# ds2.net
KiCad netlist of a schematic drawn in EAGLE
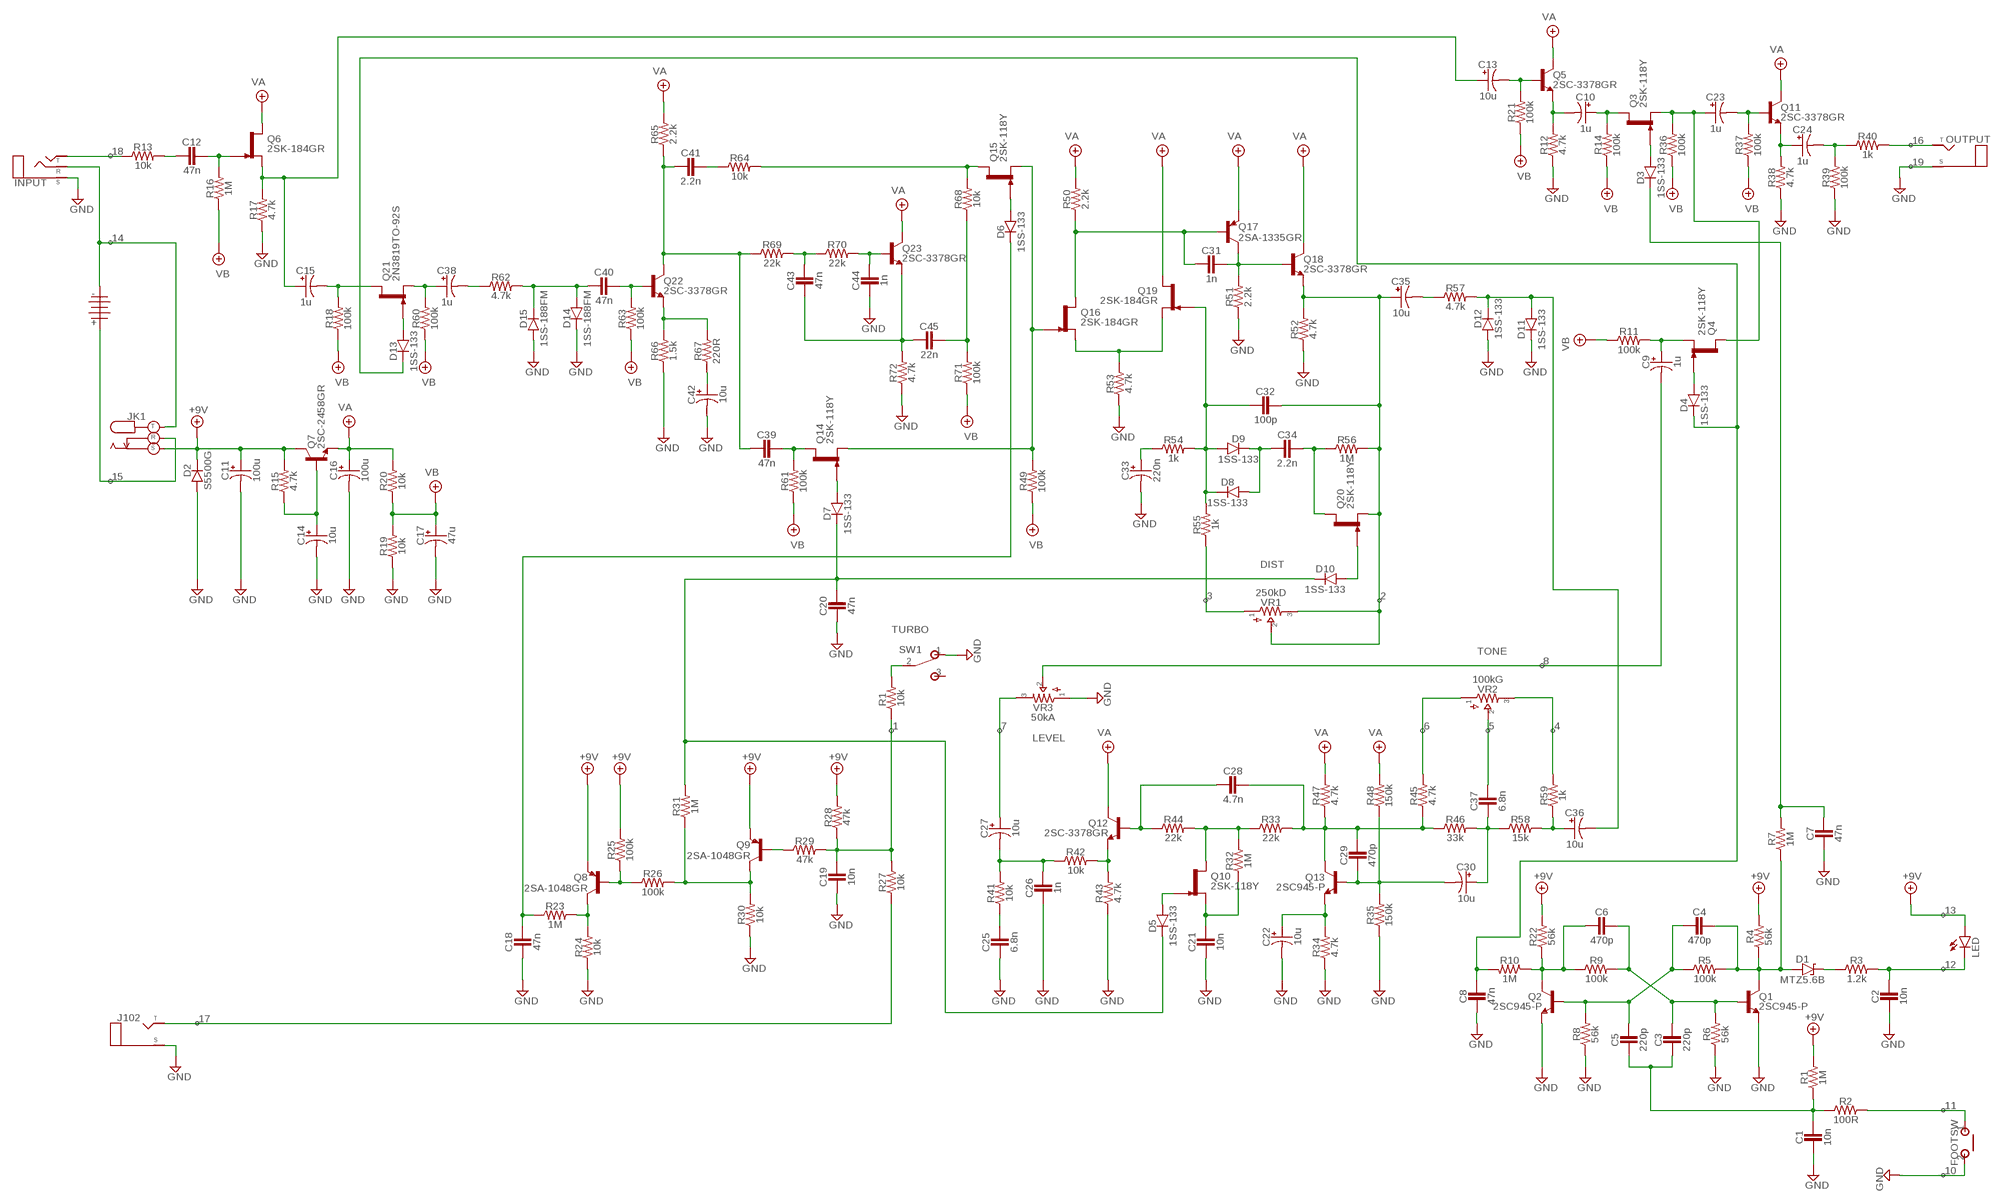
[diagram p0: schematic, sheet 1]

(export (version "E")
  (design (tool "Eeschema 10.0.6"))
  (components
    (comp (ref "1101")
      (value "BATTERY")
      (footprint "eagle-import:TWO_PADS")
      (libsource (lib "eagle-import") (part "BATTERY"))
    )
    (comp (ref "C1")
      (value "10n")
      (footprint "eagle-import:BOX_SMALL")
      (libsource (lib "eagle-import") (part "CER/FILMBOX.1"))
    )
    (comp (ref "C2")
      (value "10n")
      (footprint "eagle-import:BOX_SMALL")
      (libsource (lib "eagle-import") (part "CER/FILMBOX.1"))
    )
    (comp (ref "C3")
      (value "220p")
      (footprint "eagle-import:BOX_SMALL")
      (libsource (lib "eagle-import") (part "CER/FILMBOX.1"))
    )
    (comp (ref "C4")
      (value "470p")
      (footprint "eagle-import:BOX_SMALL")
      (libsource (lib "eagle-import") (part "CER/FILMBOX.1"))
    )
    (comp (ref "C5")
      (value "220p")
      (footprint "eagle-import:BOX_SMALL")
      (libsource (lib "eagle-import") (part "CER/FILMBOX.1"))
    )
    (comp (ref "C6")
      (value "470p")
      (footprint "eagle-import:BOX_SMALL")
      (libsource (lib "eagle-import") (part "CER/FILMBOX.1"))
    )
    (comp (ref "C7")
      (value "47n")
      (footprint "eagle-import:BOX_SMALL")
      (libsource (lib "eagle-import") (part "CER/FILMBOX.1"))
    )
    (comp (ref "C8")
      (value "47n")
      (footprint "eagle-import:BOX_SMALL")
      (libsource (lib "eagle-import") (part "CER/FILMBOX.1"))
    )
    (comp (ref "C9")
      (value "1u")
      (footprint "eagle-import:040_020")
      (libsource (lib "eagle-import") (part "0400"))
    )
    (comp (ref "C10")
      (value "1u")
      (footprint "eagle-import:040_020")
      (libsource (lib "eagle-import") (part "0400"))
    )
    (comp (ref "C11")
      (value "100u")
      (footprint "eagle-import:040_020")
      (libsource (lib "eagle-import") (part "0400"))
    )
    (comp (ref "C12")
      (value "47n")
      (footprint "eagle-import:BOX_SMALL")
      (libsource (lib "eagle-import") (part "CER/FILMBOX.1"))
    )
    (comp (ref "C13")
      (value "10u")
      (footprint "eagle-import:040_020")
      (libsource (lib "eagle-import") (part "0400"))
    )
    (comp (ref "C14")
      (value "10u")
      (footprint "eagle-import:040_020")
      (libsource (lib "eagle-import") (part "0400"))
    )
    (comp (ref "C15")
      (value "1u")
      (footprint "eagle-import:040_020")
      (libsource (lib "eagle-import") (part "0400"))
    )
    (comp (ref "C16")
      (value "100u")
      (footprint "eagle-import:040_020")
      (libsource (lib "eagle-import") (part "0400"))
    )
    (comp (ref "C17")
      (value "47u")
      (footprint "eagle-import:040_020")
      (libsource (lib "eagle-import") (part "0400"))
    )
    (comp (ref "C18")
      (value "47n")
      (footprint "eagle-import:BOX_SMALL")
      (libsource (lib "eagle-import") (part "CER/FILMBOX.1"))
    )
    (comp (ref "C19")
      (value "10n")
      (footprint "eagle-import:BOX_SMALL")
      (libsource (lib "eagle-import") (part "CER/FILMBOX.1"))
    )
    (comp (ref "C20")
      (value "47n")
      (footprint "eagle-import:BOX_SMALL")
      (libsource (lib "eagle-import") (part "CER/FILMBOX.1"))
    )
    (comp (ref "C21")
      (value "10n")
      (footprint "eagle-import:BOX_SMALL")
      (libsource (lib "eagle-import") (part "CER/FILMBOX.1"))
    )
    (comp (ref "C22")
      (value "10u")
      (footprint "eagle-import:040_020")
      (libsource (lib "eagle-import") (part "0400"))
    )
    (comp (ref "C23")
      (value "1u")
      (footprint "eagle-import:040_020")
      (libsource (lib "eagle-import") (part "0400"))
    )
    (comp (ref "C24")
      (value "1u")
      (footprint "eagle-import:040_020")
      (libsource (lib "eagle-import") (part "0400"))
    )
    (comp (ref "C25")
      (value "6.8n")
      (footprint "eagle-import:BOX_SMALL")
      (libsource (lib "eagle-import") (part "CER/FILMBOX.1"))
    )
    (comp (ref "C26")
      (value "1n")
      (footprint "eagle-import:BOX_SMALL")
      (libsource (lib "eagle-import") (part "CER/FILMBOX.1"))
    )
    (comp (ref "C27")
      (value "10u")
      (footprint "eagle-import:040_020")
      (libsource (lib "eagle-import") (part "0400"))
    )
    (comp (ref "C28")
      (value "4.7n")
      (footprint "eagle-import:BOX_SMALL")
      (libsource (lib "eagle-import") (part "CER/FILMBOX.1"))
    )
    (comp (ref "C29")
      (value "470p")
      (footprint "eagle-import:BOX_SMALL")
      (libsource (lib "eagle-import") (part "CER/FILMBOX.1"))
    )
    (comp (ref "C30")
      (value "10u")
      (footprint "eagle-import:040_020")
      (libsource (lib "eagle-import") (part "0400"))
    )
    (comp (ref "C31")
      (value "1n")
      (footprint "eagle-import:BOX_SMALL")
      (libsource (lib "eagle-import") (part "CER/FILMBOX.1"))
    )
    (comp (ref "C32")
      (value "100p")
      (footprint "eagle-import:BOX_SMALL")
      (libsource (lib "eagle-import") (part "CER/FILMBOX.1"))
    )
    (comp (ref "C33")
      (value "220n")
      (footprint "eagle-import:040_020")
      (libsource (lib "eagle-import") (part "0400"))
    )
    (comp (ref "C34")
      (value "2.2n")
      (footprint "eagle-import:BOX_SMALL")
      (libsource (lib "eagle-import") (part "CER/FILMBOX.1"))
    )
    (comp (ref "C35")
      (value "10u")
      (footprint "eagle-import:040_020")
      (libsource (lib "eagle-import") (part "0400"))
    )
    (comp (ref "C36")
      (value "10u")
      (footprint "eagle-import:040_020")
      (libsource (lib "eagle-import") (part "0400"))
    )
    (comp (ref "C37")
      (value "6.8n")
      (footprint "eagle-import:BOX_SMALL")
      (libsource (lib "eagle-import") (part "CER/FILMBOX.1"))
    )
    (comp (ref "C38")
      (value "1u")
      (footprint "eagle-import:040_020")
      (libsource (lib "eagle-import") (part "0400"))
    )
    (comp (ref "C39")
      (value "47n")
      (footprint "eagle-import:BOX_SMALL")
      (libsource (lib "eagle-import") (part "CER/FILMBOX.1"))
    )
    (comp (ref "C40")
      (value "47n")
      (footprint "eagle-import:BOX_SMALL")
      (libsource (lib "eagle-import") (part "CER/FILMBOX.1"))
    )
    (comp (ref "C41")
      (value "2.2n")
      (footprint "eagle-import:BOX_SMALL")
      (libsource (lib "eagle-import") (part "CER/FILMBOX.1"))
    )
    (comp (ref "C42")
      (value "10u")
      (footprint "eagle-import:040_020")
      (libsource (lib "eagle-import") (part "0400"))
    )
    (comp (ref "C43")
      (value "47n")
      (footprint "eagle-import:BOX_SMALL")
      (libsource (lib "eagle-import") (part "CER/FILMBOX.1"))
    )
    (comp (ref "C44")
      (value "1n")
      (footprint "eagle-import:BOX_SMALL")
      (libsource (lib "eagle-import") (part "CER/FILMBOX.1"))
    )
    (comp (ref "C45")
      (value "22n")
      (footprint "eagle-import:BOX_SMALL")
      (libsource (lib "eagle-import") (part "CER/FILMBOX.1"))
    )
    (comp (ref "D1")
      (value "MTZ5.6B")
      (footprint "eagle-import:DO41-2")
      (libsource (lib "eagle-import") (part "ZENER.2"))
    )
    (comp (ref "D2")
      (value "S5500G")
      (footprint "eagle-import:DO35-2")
      (libsource (lib "eagle-import") (part "DO35.2"))
    )
    (comp (ref "D3")
      (value "1SS-133")
      (footprint "eagle-import:DO35-2")
      (libsource (lib "eagle-import") (part "DO35.2"))
    )
    (comp (ref "D4")
      (value "1SS-133")
      (footprint "eagle-import:DO35-2")
      (libsource (lib "eagle-import") (part "DO35.2"))
    )
    (comp (ref "D5")
      (value "1SS-133")
      (footprint "eagle-import:DO35-2")
      (libsource (lib "eagle-import") (part "DO35.2"))
    )
    (comp (ref "D6")
      (value "1SS-133")
      (footprint "eagle-import:DO35-2")
      (libsource (lib "eagle-import") (part "DO35.2"))
    )
    (comp (ref "D7")
      (value "1SS-133")
      (footprint "eagle-import:DO35-2")
      (libsource (lib "eagle-import") (part "DO35.2"))
    )
    (comp (ref "D8")
      (value "1SS-133")
      (footprint "eagle-import:DO35-2")
      (libsource (lib "eagle-import") (part "DO35.2"))
    )
    (comp (ref "D9")
      (value "1SS-133")
      (footprint "eagle-import:DO35-2")
      (libsource (lib "eagle-import") (part "DO35.2"))
    )
    (comp (ref "D10")
      (value "1SS-133")
      (footprint "eagle-import:DO35-2")
      (libsource (lib "eagle-import") (part "DO35.2"))
    )
    (comp (ref "D11")
      (value "1SS-133")
      (footprint "eagle-import:DO35-2")
      (libsource (lib "eagle-import") (part "DO35.2"))
    )
    (comp (ref "D12")
      (value "1SS-133")
      (footprint "eagle-import:DO35-2")
      (libsource (lib "eagle-import") (part "DO35.2"))
    )
    (comp (ref "D13")
      (value "1SS-133")
      (footprint "eagle-import:DO35-2")
      (libsource (lib "eagle-import") (part "DO35.2"))
    )
    (comp (ref "D14")
      (value "1SS-188FM")
      (footprint "eagle-import:DO35-2")
      (libsource (lib "eagle-import") (part "DO35.2"))
    )
    (comp (ref "D15")
      (value "1SS-188FM")
      (footprint "eagle-import:DO35-2")
      (libsource (lib "eagle-import") (part "DO35.2"))
    )
    (comp (ref "FOOTSW")
      (value "MOMENTARY")
      (footprint "eagle-import:SPST")
      (libsource (lib "eagle-import") (part "MOMENTARY"))
    )
    (comp (ref "INPUT")
      (value "STEREO3PADS")
      (footprint "eagle-import:THREEPADS")
      (libsource (lib "eagle-import") (part "STEREO3PADS"))
    )
    (comp (ref "J102")
      (value "MONO")
      (footprint "eagle-import:TWO_PADS")
      (libsource (lib "eagle-import") (part "MONO"))
    )
    (comp (ref "JK1")
      (value "DC_KOBICONN")
      (footprint "eagle-import:DC_KOBICONN")
      (libsource (lib "eagle-import") (part "DC_KOBICONN"))
    )
    (comp (ref "LED")
      (value "LED")
      (footprint "eagle-import:3MM_D")
      (libsource (lib "eagle-import") (part "LED"))
    )
    (comp (ref "OUTPUT")
      (value "MONO")
      (footprint "eagle-import:TWO_PADS")
      (libsource (lib "eagle-import") (part "MONO"))
    )
    (comp (ref "Q1")
      (value "2SC945-P")
      (footprint "eagle-import:TO92-")
      (libsource (lib "eagle-import") (part "2SC828A"))
    )
    (comp (ref "Q2")
      (value "2SC945-P")
      (footprint "eagle-import:TO92-")
      (libsource (lib "eagle-import") (part "2SC828A"))
    )
    (comp (ref "Q3")
      (value "2SK-118Y")
      (footprint "eagle-import:TO92-")
      (libsource (lib "eagle-import") (part "2N3819TO-92S"))
    )
    (comp (ref "Q4")
      (value "2SK-118Y")
      (footprint "eagle-import:TO92-")
      (libsource (lib "eagle-import") (part "2N3819TO-92S"))
    )
    (comp (ref "Q5")
      (value "2SC-3378GR")
      (footprint "eagle-import:TO92-")
      (libsource (lib "eagle-import") (part "2SC828A"))
    )
    (comp (ref "Q6")
      (value "2SK-184GR")
      (footprint "eagle-import:TO92-")
      (libsource (lib "eagle-import") (part "2N3819TO-92S"))
    )
    (comp (ref "Q7")
      (value "2SC-2458GR")
      (footprint "eagle-import:TO92-")
      (libsource (lib "eagle-import") (part "2SC828A"))
    )
    (comp (ref "Q8")
      (value "2SA-1048GR")
      (footprint "eagle-import:TO92-")
      (libsource (lib "eagle-import") (part "2N3906-"))
    )
    (comp (ref "Q9")
      (value "2SA-1048GR")
      (footprint "eagle-import:TO92-")
      (libsource (lib "eagle-import") (part "2N3906-"))
    )
    (comp (ref "Q10")
      (value "2SK-118Y")
      (footprint "eagle-import:TO92-")
      (libsource (lib "eagle-import") (part "2N3819TO-92S"))
    )
    (comp (ref "Q11")
      (value "2SC-3378GR")
      (footprint "eagle-import:TO92-")
      (libsource (lib "eagle-import") (part "2SC828A"))
    )
    (comp (ref "Q12")
      (value "2SC-3378GR")
      (footprint "eagle-import:TO92-")
      (libsource (lib "eagle-import") (part "2SC828A"))
    )
    (comp (ref "Q13")
      (value "2SC945-P")
      (footprint "eagle-import:TO92-")
      (libsource (lib "eagle-import") (part "2SC828A"))
    )
    (comp (ref "Q14")
      (value "2SK-118Y")
      (footprint "eagle-import:TO92-")
      (libsource (lib "eagle-import") (part "2N3819TO-92S"))
    )
    (comp (ref "Q15")
      (value "2SK-118Y")
      (footprint "eagle-import:TO92-")
      (libsource (lib "eagle-import") (part "2N3819TO-92S"))
    )
    (comp (ref "Q16")
      (value "2SK-184GR")
      (footprint "eagle-import:TO92-")
      (libsource (lib "eagle-import") (part "2N3819TO-92S"))
    )
    (comp (ref "Q17")
      (value "2SA-1335GR")
      (footprint "eagle-import:TO92-")
      (libsource (lib "eagle-import") (part "2N3906-"))
    )
    (comp (ref "Q18")
      (value "2SC-3378GR")
      (footprint "eagle-import:TO92-")
      (libsource (lib "eagle-import") (part "2SC828A"))
    )
    (comp (ref "Q19")
      (value "2SK-184GR")
      (footprint "eagle-import:TO92-")
      (libsource (lib "eagle-import") (part "2N3819TO-92S"))
    )
    (comp (ref "Q20")
      (value "2SK-118Y")
      (footprint "eagle-import:TO92-")
      (libsource (lib "eagle-import") (part "2N3819TO-92S"))
    )
    (comp (ref "Q21")
      (value "2N3819TO-92S")
      (footprint "eagle-import:TO92-")
      (libsource (lib "eagle-import") (part "2N3819TO-92S"))
    )
    (comp (ref "Q22")
      (value "2SC-3378GR")
      (footprint "eagle-import:TO92-")
      (libsource (lib "eagle-import") (part "2SC828A"))
    )
    (comp (ref "Q23")
      (value "2SC-3378GR")
      (footprint "eagle-import:TO92-")
      (libsource (lib "eagle-import") (part "2SC828A"))
    )
    (comp (ref "R1")
      (value "1M")
      (footprint "eagle-import:R0207_3")
      (libsource (lib "eagle-import") (part "R_.3B"))
    )
    (comp (ref "R1 ")
      (value "10k")
      (footprint "eagle-import:R0207_3")
      (libsource (lib "eagle-import") (part "R_.3B"))
    )
    (comp (ref "R2")
      (value "100R")
      (footprint "eagle-import:R0207_3")
      (libsource (lib "eagle-import") (part "R_.3B"))
    )
    (comp (ref "R3")
      (value "1.2k")
      (footprint "eagle-import:R0207_3")
      (libsource (lib "eagle-import") (part "R_.3B"))
    )
    (comp (ref "R4")
      (value "56k")
      (footprint "eagle-import:R0207_3")
      (libsource (lib "eagle-import") (part "R_.3B"))
    )
    (comp (ref "R5")
      (value "100k")
      (footprint "eagle-import:R0207_3")
      (libsource (lib "eagle-import") (part "R_.3B"))
    )
    (comp (ref "R6")
      (value "56k")
      (footprint "eagle-import:R0207_3")
      (libsource (lib "eagle-import") (part "R_.3B"))
    )
    (comp (ref "R7")
      (value "1M")
      (footprint "eagle-import:R0207_3")
      (libsource (lib "eagle-import") (part "R_.3B"))
    )
    (comp (ref "R8")
      (value "56k")
      (footprint "eagle-import:R0207_3")
      (libsource (lib "eagle-import") (part "R_.3B"))
    )
    (comp (ref "R9")
      (value "100k")
      (footprint "eagle-import:R0207_3")
      (libsource (lib "eagle-import") (part "R_.3B"))
    )
    (comp (ref "R10")
      (value "1M")
      (footprint "eagle-import:R0207_3")
      (libsource (lib "eagle-import") (part "R_.3B"))
    )
    (comp (ref "R11")
      (value "100k")
      (footprint "eagle-import:R0207_3")
      (libsource (lib "eagle-import") (part "R_.3B"))
    )
    (comp (ref "R12")
      (value "4.7k")
      (footprint "eagle-import:R0207_3")
      (libsource (lib "eagle-import") (part "R_.3B"))
    )
    (comp (ref "R13")
      (value "10k")
      (footprint "eagle-import:R0207_3")
      (libsource (lib "eagle-import") (part "R_.3B"))
    )
    (comp (ref "R14")
      (value "100k")
      (footprint "eagle-import:R0207_3")
      (libsource (lib "eagle-import") (part "R_.3B"))
    )
    (comp (ref "R15")
      (value "4.7k")
      (footprint "eagle-import:R0207_3")
      (libsource (lib "eagle-import") (part "R_.3B"))
    )
    (comp (ref "R16")
      (value "1M")
      (footprint "eagle-import:R0207_3")
      (libsource (lib "eagle-import") (part "R_.3B"))
    )
    (comp (ref "R17")
      (value "4.7k")
      (footprint "eagle-import:R0207_3")
      (libsource (lib "eagle-import") (part "R_.3B"))
    )
    (comp (ref "R18")
      (value "100k")
      (footprint "eagle-import:R0207_3")
      (libsource (lib "eagle-import") (part "R_.3B"))
    )
    (comp (ref "R19")
      (value "10k")
      (footprint "eagle-import:R0207_3")
      (libsource (lib "eagle-import") (part "R_.3B"))
    )
    (comp (ref "R20")
      (value "10k")
      (footprint "eagle-import:R0207_3")
      (libsource (lib "eagle-import") (part "R_.3B"))
    )
    (comp (ref "R21")
      (value "100k")
      (footprint "eagle-import:R0207_3")
      (libsource (lib "eagle-import") (part "R_.3B"))
    )
    (comp (ref "R22")
      (value "56k")
      (footprint "eagle-import:R0207_3")
      (libsource (lib "eagle-import") (part "R_.3B"))
    )
    (comp (ref "R23")
      (value "1M")
      (footprint "eagle-import:R0207_3")
      (libsource (lib "eagle-import") (part "R_.3B"))
    )
    (comp (ref "R24")
      (value "10k")
      (footprint "eagle-import:R0207_3")
      (libsource (lib "eagle-import") (part "R_.3B"))
    )
    (comp (ref "R25")
      (value "100k")
      (footprint "eagle-import:R0207_3")
      (libsource (lib "eagle-import") (part "R_.3B"))
    )
    (comp (ref "R26")
      (value "100k")
      (footprint "eagle-import:R0207_3")
      (libsource (lib "eagle-import") (part "R_.3B"))
    )
    (comp (ref "R27")
      (value "10k")
      (footprint "eagle-import:R0207_3")
      (libsource (lib "eagle-import") (part "R_.3B"))
    )
    (comp (ref "R28")
      (value "47k")
      (footprint "eagle-import:R0207_3")
      (libsource (lib "eagle-import") (part "R_.3B"))
    )
    (comp (ref "R29")
      (value "47k")
      (footprint "eagle-import:R0207_3")
      (libsource (lib "eagle-import") (part "R_.3B"))
    )
    (comp (ref "R30")
      (value "10k")
      (footprint "eagle-import:R0207_3")
      (libsource (lib "eagle-import") (part "R_.3B"))
    )
    (comp (ref "R31")
      (value "1M")
      (footprint "eagle-import:R0207_3")
      (libsource (lib "eagle-import") (part "R_.3B"))
    )
    (comp (ref "R32")
      (value "1M")
      (footprint "eagle-import:R0207_3")
      (libsource (lib "eagle-import") (part "R_.3B"))
    )
    (comp (ref "R33")
      (value "22k")
      (footprint "eagle-import:R0207_3")
      (libsource (lib "eagle-import") (part "R_.3B"))
    )
    (comp (ref "R34")
      (value "4.7k")
      (footprint "eagle-import:R0207_3")
      (libsource (lib "eagle-import") (part "R_.3B"))
    )
    (comp (ref "R35")
      (value "150k")
      (footprint "eagle-import:R0207_3")
      (libsource (lib "eagle-import") (part "R_.3B"))
    )
    (comp (ref "R36")
      (value "100k")
      (footprint "eagle-import:R0207_3")
      (libsource (lib "eagle-import") (part "R_.3B"))
    )
    (comp (ref "R37")
      (value "100k")
      (footprint "eagle-import:R0207_3")
      (libsource (lib "eagle-import") (part "R_.3B"))
    )
    (comp (ref "R38")
      (value "4.7k")
      (footprint "eagle-import:R0207_3")
      (libsource (lib "eagle-import") (part "R_.3B"))
    )
    (comp (ref "R39")
      (value "100k")
      (footprint "eagle-import:R0207_3")
      (libsource (lib "eagle-import") (part "R_.3B"))
    )
    (comp (ref "R40")
      (value "1k")
      (footprint "eagle-import:R0207_3")
      (libsource (lib "eagle-import") (part "R_.3B"))
    )
    (comp (ref "R41")
      (value "10k")
      (footprint "eagle-import:R0207_3")
      (libsource (lib "eagle-import") (part "R_.3B"))
    )
    (comp (ref "R42")
      (value "10k")
      (footprint "eagle-import:R0207_3")
      (libsource (lib "eagle-import") (part "R_.3B"))
    )
    (comp (ref "R43")
      (value "4.7k")
      (footprint "eagle-import:R0207_3")
      (libsource (lib "eagle-import") (part "R_.3B"))
    )
    (comp (ref "R44")
      (value "22k")
      (footprint "eagle-import:R0207_3")
      (libsource (lib "eagle-import") (part "R_.3B"))
    )
    (comp (ref "R45")
      (value "4.7k")
      (footprint "eagle-import:R0207_3")
      (libsource (lib "eagle-import") (part "R_.3B"))
    )
    (comp (ref "R46")
      (value "33k")
      (footprint "eagle-import:R0207_3")
      (libsource (lib "eagle-import") (part "R_.3B"))
    )
    (comp (ref "R47")
      (value "4.7k")
      (footprint "eagle-import:R0207_3")
      (libsource (lib "eagle-import") (part "R_.3B"))
    )
    (comp (ref "R48")
      (value "150k")
      (footprint "eagle-import:R0207_3")
      (libsource (lib "eagle-import") (part "R_.3B"))
    )
    (comp (ref "R49")
      (value "100k")
      (footprint "eagle-import:R0207_3")
      (libsource (lib "eagle-import") (part "R_.3B"))
    )
    (comp (ref "R50")
      (value "2.2k")
      (footprint "eagle-import:R0207_3")
      (libsource (lib "eagle-import") (part "R_.3B"))
    )
    (comp (ref "R51")
      (value "2.2k")
      (footprint "eagle-import:R0207_3")
      (libsource (lib "eagle-import") (part "R_.3B"))
    )
    (comp (ref "R52")
      (value "4.7k")
      (footprint "eagle-import:R0207_3")
      (libsource (lib "eagle-import") (part "R_.3B"))
    )
    (comp (ref "R53")
      (value "4.7k")
      (footprint "eagle-import:R0207_3")
      (libsource (lib "eagle-import") (part "R_.3B"))
    )
    (comp (ref "R54")
      (value "1k")
      (footprint "eagle-import:R0207_3")
      (libsource (lib "eagle-import") (part "R_.3B"))
    )
    (comp (ref "R55")
      (value "1k")
      (footprint "eagle-import:R0207_3")
      (libsource (lib "eagle-import") (part "R_.3B"))
    )
    (comp (ref "R56")
      (value "1M")
      (footprint "eagle-import:R0207_3")
      (libsource (lib "eagle-import") (part "R_.3B"))
    )
    (comp (ref "R57")
      (value "4.7k")
      (footprint "eagle-import:R0207_3")
      (libsource (lib "eagle-import") (part "R_.3B"))
    )
    (comp (ref "R58")
      (value "15k")
      (footprint "eagle-import:R0207_3")
      (libsource (lib "eagle-import") (part "R_.3B"))
    )
    (comp (ref "R59")
      (value "1k")
      (footprint "eagle-import:R0207_3")
      (libsource (lib "eagle-import") (part "R_.3B"))
    )
    (comp (ref "R60")
      (value "100k")
      (footprint "eagle-import:R0207_3")
      (libsource (lib "eagle-import") (part "R_.3B"))
    )
    (comp (ref "R61")
      (value "100k")
      (footprint "eagle-import:R0207_3")
      (libsource (lib "eagle-import") (part "R_.3B"))
    )
    (comp (ref "R62")
      (value "4.7k")
      (footprint "eagle-import:R0207_3")
      (libsource (lib "eagle-import") (part "R_.3B"))
    )
    (comp (ref "R63")
      (value "100k")
      (footprint "eagle-import:R0207_3")
      (libsource (lib "eagle-import") (part "R_.3B"))
    )
    (comp (ref "R64")
      (value "10k")
      (footprint "eagle-import:R0207_3")
      (libsource (lib "eagle-import") (part "R_.3B"))
    )
    (comp (ref "R65")
      (value "2.2k")
      (footprint "eagle-import:R0207_3")
      (libsource (lib "eagle-import") (part "R_.3B"))
    )
    (comp (ref "R66")
      (value "1.5k")
      (footprint "eagle-import:R0207_3")
      (libsource (lib "eagle-import") (part "R_.3B"))
    )
    (comp (ref "R67")
      (value "220R")
      (footprint "eagle-import:R0207_3")
      (libsource (lib "eagle-import") (part "R_.3B"))
    )
    (comp (ref "R68")
      (value "10k")
      (footprint "eagle-import:R0207_3")
      (libsource (lib "eagle-import") (part "R_.3B"))
    )
    (comp (ref "R69")
      (value "22k")
      (footprint "eagle-import:R0207_3")
      (libsource (lib "eagle-import") (part "R_.3B"))
    )
    (comp (ref "R70")
      (value "22k")
      (footprint "eagle-import:R0207_3")
      (libsource (lib "eagle-import") (part "R_.3B"))
    )
    (comp (ref "R71")
      (value "100k")
      (footprint "eagle-import:R0207_3")
      (libsource (lib "eagle-import") (part "R_.3B"))
    )
    (comp (ref "R72")
      (value "4.7k")
      (footprint "eagle-import:R0207_3")
      (libsource (lib "eagle-import") (part "R_.3B"))
    )
    (comp (ref "SW1")
      (value "SPDT")
      (footprint "eagle-import:M9040P")
      (libsource (lib "eagle-import") (part "SPDT"))
    )
    (comp (ref "VR1")
      (value "250kD")
      (footprint "eagle-import:16MM")
      (libsource (lib "eagle-import") (part "POTS16MM"))
    )
    (comp (ref "VR2")
      (value "100kG")
      (footprint "eagle-import:16MM")
      (libsource (lib "eagle-import") (part "POTS16MM"))
    )
    (comp (ref "VR3")
      (value "50kA")
      (footprint "eagle-import:16MM")
      (libsource (lib "eagle-import") (part "POTS16MM"))
    )
  )
  (nets
    (net (code "1") (name "+9V") (class "Default")
      (node (ref "C11") (pin "+") (pinfunction "+_+") (pintype "passive"))
      (node (ref "D2") (pin "C") (pinfunction "C_C") (pintype "passive"))
      (node (ref "JK1") (pin "S") (pinfunction "S_S") (pintype "bidirectional"))
      (node (ref "LED") (pin "ANODE") (pinfunction "A_ANODE") (pintype "passive"))
      (node (ref "Q7") (pin "2") (pinfunction "C_2") (pintype "passive"))
      (node (ref "Q8") (pin "3") (pinfunction "E_3") (pintype "passive"))
      (node (ref "Q9") (pin "3") (pinfunction "E_3") (pintype "passive"))
      (node (ref "R1") (pin "2") (pinfunction "2_2") (pintype "passive"))
      (node (ref "R15") (pin "2") (pinfunction "2_2") (pintype "passive"))
      (node (ref "R22") (pin "2") (pinfunction "2_2") (pintype "passive"))
      (node (ref "R25") (pin "2") (pinfunction "2_2") (pintype "passive"))
      (node (ref "R28") (pin "2") (pinfunction "2_2") (pintype "passive"))
      (node (ref "R4") (pin "2") (pinfunction "2_2") (pintype "passive"))
    )
    (net (code "2") (name "GND") (class "Default")
      (node (ref "C1") (pin "2") (pinfunction "2_2") (pintype "passive"))
      (node (ref "C11") (pin "-") (pinfunction "-_-") (pintype "passive"))
      (node (ref "C14") (pin "-") (pinfunction "-_-") (pintype "passive"))
      (node (ref "C16") (pin "-") (pinfunction "-_-") (pintype "passive"))
      (node (ref "C17") (pin "-") (pinfunction "-_-") (pintype "passive"))
      (node (ref "C18") (pin "2") (pinfunction "2_2") (pintype "passive"))
      (node (ref "C19") (pin "2") (pinfunction "2_2") (pintype "passive"))
      (node (ref "C2") (pin "2") (pinfunction "2_2") (pintype "passive"))
      (node (ref "C20") (pin "2") (pinfunction "2_2") (pintype "passive"))
      (node (ref "C21") (pin "2") (pinfunction "2_2") (pintype "passive"))
      (node (ref "C22") (pin "-") (pinfunction "-_-") (pintype "passive"))
      (node (ref "C25") (pin "2") (pinfunction "2_2") (pintype "passive"))
      (node (ref "C26") (pin "2") (pinfunction "2_2") (pintype "passive"))
      (node (ref "C33") (pin "-") (pinfunction "-_-") (pintype "passive"))
      (node (ref "C42") (pin "-") (pinfunction "-_-") (pintype "passive"))
      (node (ref "C44") (pin "2") (pinfunction "2_2") (pintype "passive"))
      (node (ref "C7") (pin "2") (pinfunction "2_2") (pintype "passive"))
      (node (ref "C8") (pin "2") (pinfunction "2_2") (pintype "passive"))
      (node (ref "D11") (pin "C") (pinfunction "C_C") (pintype "passive"))
      (node (ref "D12") (pin "A") (pinfunction "A_A") (pintype "passive"))
      (node (ref "D14") (pin "C") (pinfunction "C_C") (pintype "passive"))
      (node (ref "D15") (pin "A") (pinfunction "A_A") (pintype "passive"))
      (node (ref "D2") (pin "A") (pinfunction "A_A") (pintype "passive"))
      (node (ref "FOOTSW") (pin "2") (pinfunction "S_2") (pintype "passive"))
      (node (ref "INPUT") (pin "SLEEVE") (pinfunction "S_SLEEVE") (pintype "passive"))
      (node (ref "J102") (pin "S") (pinfunction "SLEEVE_S") (pintype "passive"))
      (node (ref "OUTPUT") (pin "S") (pinfunction "SLEEVE_S") (pintype "passive"))
      (node (ref "Q1") (pin "3") (pinfunction "E_3") (pintype "passive"))
      (node (ref "Q2") (pin "3") (pinfunction "E_3") (pintype "passive"))
      (node (ref "R12") (pin "1") (pinfunction "1_1") (pintype "passive"))
      (node (ref "R17") (pin "1") (pinfunction "1_1") (pintype "passive"))
      (node (ref "R19") (pin "1") (pinfunction "1_1") (pintype "passive"))
      (node (ref "R24") (pin "1") (pinfunction "1_1") (pintype "passive"))
      (node (ref "R30") (pin "1") (pinfunction "1_1") (pintype "passive"))
      (node (ref "R34") (pin "1") (pinfunction "1_1") (pintype "passive"))
      (node (ref "R35") (pin "1") (pinfunction "1_1") (pintype "passive"))
      (node (ref "R38") (pin "1") (pinfunction "1_1") (pintype "passive"))
      (node (ref "R39") (pin "1") (pinfunction "1_1") (pintype "passive"))
      (node (ref "R43") (pin "1") (pinfunction "1_1") (pintype "passive"))
      (node (ref "R51") (pin "1") (pinfunction "1_1") (pintype "passive"))
      (node (ref "R52") (pin "1") (pinfunction "1_1") (pintype "passive"))
      (node (ref "R53") (pin "1") (pinfunction "1_1") (pintype "passive"))
      (node (ref "R6") (pin "1") (pinfunction "1_1") (pintype "passive"))
      (node (ref "R66") (pin "1") (pinfunction "1_1") (pintype "passive"))
      (node (ref "R72") (pin "1") (pinfunction "1_1") (pintype "passive"))
      (node (ref "R8") (pin "1") (pinfunction "1_1") (pintype "passive"))
      (node (ref "SW1") (pin "1") (pinfunction "O_1") (pintype "passive"))
      (node (ref "VR3") (pin "1") (pinfunction "1_1") (pintype "passive"))
    )
    (net (code "3") (name "Net-(1101-P$1)") (class "Default")
      (node (ref "1101") (pin "T") (pinfunction "P$1_T") (pintype "bidirectional"))
      (node (ref "JK1") (pin "R") (pinfunction "R_R") (pintype "bidirectional"))
    )
    (net (code "4") (name "Net-(1101-P$2)") (class "Default")
      (node (ref "1101") (pin "S") (pinfunction "P$2_S") (pintype "bidirectional"))
      (node (ref "INPUT") (pin "RING") (pinfunction "R_RING") (pintype "passive"))
      (node (ref "JK1") (pin "T") (pinfunction "T_T") (pintype "bidirectional"))
    )
    (net (code "5") (name "Net-(C1-Pad1)") (class "Default")
      (node (ref "C1") (pin "1") (pinfunction "1_1") (pintype "passive"))
      (node (ref "C3") (pin "2") (pinfunction "2_2") (pintype "passive"))
      (node (ref "C5") (pin "2") (pinfunction "2_2") (pintype "passive"))
      (node (ref "R1") (pin "1") (pinfunction "1_1") (pintype "passive"))
      (node (ref "R2") (pin "1") (pinfunction "1_1") (pintype "passive"))
    )
    (net (code "6") (name "Net-(C7-Pad1)") (class "Default")
      (node (ref "C7") (pin "1") (pinfunction "1_1") (pintype "passive"))
      (node (ref "D3") (pin "C") (pinfunction "C_C") (pintype "passive"))
      (node (ref "R7") (pin "2") (pinfunction "2_2") (pintype "passive"))
    )
    (net (code "7") (name "Net-(C8-Pad1)") (class "Default")
      (node (ref "C8") (pin "1") (pinfunction "1_1") (pintype "passive"))
      (node (ref "D13") (pin "C") (pinfunction "C_C") (pintype "passive"))
      (node (ref "D4") (pin "C") (pinfunction "C_C") (pintype "passive"))
      (node (ref "R10") (pin "2") (pinfunction "2_2") (pintype "passive"))
    )
    (net (code "8") (name "Net-(C9-Pad-)") (class "Default")
      (node (ref "C9") (pin "-") (pinfunction "-_-") (pintype "passive"))
      (node (ref "VR3") (pin "2") (pinfunction "2_2") (pintype "passive"))
    )
    (net (code "9") (name "Net-(C12-Pad2)") (class "Default")
      (node (ref "C12") (pin "2") (pinfunction "2_2") (pintype "passive"))
      (node (ref "R13") (pin "2") (pinfunction "2_2") (pintype "passive"))
    )
    (net (code "10") (name "Net-(C18-Pad1)") (class "Default")
      (node (ref "C18") (pin "1") (pinfunction "1_1") (pintype "passive"))
      (node (ref "D6") (pin "C") (pinfunction "C_C") (pintype "passive"))
      (node (ref "R23") (pin "1") (pinfunction "1_1") (pintype "passive"))
    )
    (net (code "11") (name "Net-(C19-Pad1)") (class "Default")
      (node (ref "C19") (pin "1") (pinfunction "1_1") (pintype "passive"))
      (node (ref "R1 ") (pin "1") (pinfunction "1_1") (pintype "passive"))
      (node (ref "R27") (pin "2") (pinfunction "2_2") (pintype "passive"))
      (node (ref "R28") (pin "1") (pinfunction "1_1") (pintype "passive"))
      (node (ref "R29") (pin "2") (pinfunction "2_2") (pintype "passive"))
    )
    (net (code "12") (name "Net-(C20-Pad1)") (class "Default")
      (node (ref "C20") (pin "1") (pinfunction "1_1") (pintype "passive"))
      (node (ref "D10") (pin "C") (pinfunction "C_C") (pintype "passive"))
      (node (ref "D5") (pin "C") (pinfunction "C_C") (pintype "passive"))
      (node (ref "D7") (pin "C") (pinfunction "C_C") (pintype "passive"))
      (node (ref "R31") (pin "2") (pinfunction "2_2") (pintype "passive"))
    )
    (net (code "13") (name "Net-(C24-Pad-)") (class "Default")
      (node (ref "C24") (pin "-") (pinfunction "-_-") (pintype "passive"))
      (node (ref "R39") (pin "2") (pinfunction "2_2") (pintype "passive"))
      (node (ref "R40") (pin "1") (pinfunction "1_1") (pintype "passive"))
    )
    (net (code "14") (name "Net-(C25-Pad1)") (class "Default")
      (node (ref "C25") (pin "1") (pinfunction "1_1") (pintype "passive"))
      (node (ref "R41") (pin "1") (pinfunction "1_1") (pintype "passive"))
    )
    (net (code "15") (name "Net-(C26-Pad1)") (class "Default")
      (node (ref "C26") (pin "1") (pinfunction "1_1") (pintype "passive"))
      (node (ref "C27") (pin "-") (pinfunction "-_-") (pintype "passive"))
      (node (ref "R41") (pin "2") (pinfunction "2_2") (pintype "passive"))
      (node (ref "R42") (pin "1") (pinfunction "1_1") (pintype "passive"))
    )
    (net (code "16") (name "Net-(C27-Pad+)") (class "Default")
      (node (ref "C27") (pin "+") (pinfunction "+_+") (pintype "passive"))
      (node (ref "VR3") (pin "3") (pinfunction "3_3") (pintype "passive"))
    )
    (net (code "17") (name "Net-(C30-Pad+)") (class "Default")
      (node (ref "C30") (pin "+") (pinfunction "+_+") (pintype "passive"))
      (node (ref "C37") (pin "2") (pinfunction "2_2") (pintype "passive"))
      (node (ref "R46") (pin "2") (pinfunction "2_2") (pintype "passive"))
      (node (ref "R58") (pin "1") (pinfunction "1_1") (pintype "passive"))
    )
    (net (code "18") (name "Net-(C33-Pad+)") (class "Default")
      (node (ref "C33") (pin "+") (pinfunction "+_+") (pintype "passive"))
      (node (ref "R54") (pin "1") (pinfunction "1_1") (pintype "passive"))
    )
    (net (code "19") (name "Net-(C34-Pad2)") (class "Default")
      (node (ref "C34") (pin "2") (pinfunction "2_2") (pintype "passive"))
      (node (ref "D8") (pin "A") (pinfunction "A_A") (pintype "passive"))
      (node (ref "D9") (pin "C") (pinfunction "C_C") (pintype "passive"))
    )
    (net (code "20") (name "Net-(C35-Pad-)") (class "Default")
      (node (ref "C35") (pin "-") (pinfunction "-_-") (pintype "passive"))
      (node (ref "R57") (pin "1") (pinfunction "1_1") (pintype "passive"))
    )
    (net (code "21") (name "Net-(C36-Pad+)") (class "Default")
      (node (ref "C36") (pin "+") (pinfunction "+_+") (pintype "passive"))
      (node (ref "R58") (pin "2") (pinfunction "2_2") (pintype "passive"))
      (node (ref "R59") (pin "1") (pinfunction "1_1") (pintype "passive"))
    )
    (net (code "22") (name "Net-(C36-Pad-)") (class "Default")
      (node (ref "C36") (pin "-") (pinfunction "-_-") (pintype "passive"))
      (node (ref "D11") (pin "A") (pinfunction "A_A") (pintype "passive"))
      (node (ref "D12") (pin "C") (pinfunction "C_C") (pintype "passive"))
      (node (ref "R57") (pin "2") (pinfunction "2_2") (pintype "passive"))
    )
    (net (code "23") (name "Net-(C37-Pad1)") (class "Default")
      (node (ref "C37") (pin "1") (pinfunction "1_1") (pintype "passive"))
      (node (ref "VR2") (pin "2") (pinfunction "2_2") (pintype "passive"))
    )
    (net (code "24") (name "Net-(C38-Pad-)") (class "Default")
      (node (ref "C38") (pin "-") (pinfunction "-_-") (pintype "passive"))
      (node (ref "R62") (pin "1") (pinfunction "1_1") (pintype "passive"))
    )
    (net (code "25") (name "Net-(C40-Pad2)") (class "Default")
      (node (ref "C40") (pin "2") (pinfunction "2_2") (pintype "passive"))
      (node (ref "D14") (pin "A") (pinfunction "A_A") (pintype "passive"))
      (node (ref "D15") (pin "C") (pinfunction "C_C") (pintype "passive"))
      (node (ref "R62") (pin "2") (pinfunction "2_2") (pintype "passive"))
    )
    (net (code "26") (name "Net-(C41-Pad1)") (class "Default")
      (node (ref "C41") (pin "1") (pinfunction "1_1") (pintype "passive"))
      (node (ref "R64") (pin "1") (pinfunction "1_1") (pintype "passive"))
    )
    (net (code "27") (name "Net-(C42-Pad+)") (class "Default")
      (node (ref "C42") (pin "+") (pinfunction "+_+") (pintype "passive"))
      (node (ref "R67") (pin "1") (pinfunction "1_1") (pintype "passive"))
    )
    (net (code "28") (name "Net-(C43-Pad1)") (class "Default")
      (node (ref "C43") (pin "1") (pinfunction "1_1") (pintype "passive"))
      (node (ref "R69") (pin "2") (pinfunction "2_2") (pintype "passive"))
      (node (ref "R70") (pin "1") (pinfunction "1_1") (pintype "passive"))
    )
    (net (code "29") (name "Net-(C45-Pad1)") (class "Default")
      (node (ref "C45") (pin "1") (pinfunction "1_1") (pintype "passive"))
      (node (ref "R68") (pin "1") (pinfunction "1_1") (pintype "passive"))
      (node (ref "R71") (pin "2") (pinfunction "2_2") (pintype "passive"))
    )
    (net (code "30") (name "Net-(D1-PadC)") (class "Default")
      (node (ref "D1") (pin "C") (pinfunction "C_C") (pintype "passive"))
      (node (ref "R3") (pin "1") (pinfunction "1_1") (pintype "passive"))
    )
    (net (code "31") (name "Net-(FOOTSW-P)") (class "Default")
      (node (ref "FOOTSW") (pin "1") (pinfunction "P_1") (pintype "passive"))
      (node (ref "R2") (pin "2") (pinfunction "2_2") (pintype "passive"))
    )
    (net (code "32") (name "Net-(INPUT-T)") (class "Default")
      (node (ref "INPUT") (pin "TIP") (pinfunction "T_TIP") (pintype "passive"))
      (node (ref "R13") (pin "1") (pinfunction "1_1") (pintype "passive"))
    )
    (net (code "33") (name "Net-(J102-TIP)") (class "Default")
      (node (ref "J102") (pin "T") (pinfunction "TIP_T") (pintype "passive"))
      (node (ref "R27") (pin "1") (pinfunction "1_1") (pintype "passive"))
    )
    (net (code "34") (name "Net-(LED-C)") (class "Default")
      (node (ref "C2") (pin "1") (pinfunction "1_1") (pintype "passive"))
      (node (ref "LED") (pin "P$1") (pinfunction "C_P$1") (pintype "passive"))
      (node (ref "R3") (pin "2") (pinfunction "2_2") (pintype "passive"))
    )
    (net (code "35") (name "Net-(OUTPUT-TIP)") (class "Default")
      (node (ref "OUTPUT") (pin "T") (pinfunction "TIP_T") (pintype "passive"))
      (node (ref "R40") (pin "2") (pinfunction "2_2") (pintype "passive"))
    )
    (net (code "36") (name "Net-(Q1-B)") (class "Default")
      (node (ref "C3") (pin "1") (pinfunction "1_1") (pintype "passive"))
      (node (ref "C6") (pin "1") (pinfunction "1_1") (pintype "passive"))
      (node (ref "Q1") (pin "1") (pinfunction "B_1") (pintype "passive"))
      (node (ref "R6") (pin "2") (pinfunction "2_2") (pintype "passive"))
      (node (ref "R9") (pin "2") (pinfunction "2_2") (pintype "passive"))
    )
    (net (code "37") (name "Net-(Q1-C)") (class "Default")
      (node (ref "C4") (pin "1") (pinfunction "1_1") (pintype "passive"))
      (node (ref "D1") (pin "A") (pinfunction "A_A") (pintype "passive"))
      (node (ref "Q1") (pin "2") (pinfunction "C_2") (pintype "passive"))
      (node (ref "R4") (pin "1") (pinfunction "1_1") (pintype "passive"))
      (node (ref "R5") (pin "2") (pinfunction "2_2") (pintype "passive"))
      (node (ref "R7") (pin "1") (pinfunction "1_1") (pintype "passive"))
    )
    (net (code "38") (name "Net-(Q2-B)") (class "Default")
      (node (ref "C4") (pin "2") (pinfunction "2_2") (pintype "passive"))
      (node (ref "C5") (pin "1") (pinfunction "1_1") (pintype "passive"))
      (node (ref "Q2") (pin "1") (pinfunction "B_1") (pintype "passive"))
      (node (ref "R5") (pin "1") (pinfunction "1_1") (pintype "passive"))
      (node (ref "R8") (pin "2") (pinfunction "2_2") (pintype "passive"))
    )
    (net (code "39") (name "Net-(Q2-C)") (class "Default")
      (node (ref "C6") (pin "2") (pinfunction "2_2") (pintype "passive"))
      (node (ref "Q2") (pin "2") (pinfunction "C_2") (pintype "passive"))
      (node (ref "R10") (pin "1") (pinfunction "1_1") (pintype "passive"))
      (node (ref "R22") (pin "1") (pinfunction "1_1") (pintype "passive"))
      (node (ref "R9") (pin "1") (pinfunction "1_1") (pintype "passive"))
    )
    (net (code "40") (name "Net-(Q3-D)") (class "Default")
      (node (ref "C10") (pin "+") (pinfunction "+_+") (pintype "passive"))
      (node (ref "Q3") (pin "3") (pinfunction "D_3") (pintype "passive"))
      (node (ref "R14") (pin "2") (pinfunction "2_2") (pintype "passive"))
    )
    (net (code "41") (name "Net-(Q3-G)") (class "Default")
      (node (ref "D3") (pin "A") (pinfunction "A_A") (pintype "passive"))
      (node (ref "Q3") (pin "2") (pinfunction "G_2") (pintype "passive"))
    )
    (net (code "42") (name "Net-(Q3-S)") (class "Default")
      (node (ref "C23") (pin "+") (pinfunction "+_+") (pintype "passive"))
      (node (ref "Q3") (pin "1") (pinfunction "S_1") (pintype "passive"))
      (node (ref "Q4") (pin "3") (pinfunction "D_3") (pintype "passive"))
      (node (ref "R36") (pin "2") (pinfunction "2_2") (pintype "passive"))
    )
    (net (code "43") (name "Net-(Q4-G)") (class "Default")
      (node (ref "D4") (pin "A") (pinfunction "A_A") (pintype "passive"))
      (node (ref "Q4") (pin "2") (pinfunction "G_2") (pintype "passive"))
    )
    (net (code "44") (name "Net-(Q4-S)") (class "Default")
      (node (ref "C9") (pin "+") (pinfunction "+_+") (pintype "passive"))
      (node (ref "Q4") (pin "1") (pinfunction "S_1") (pintype "passive"))
      (node (ref "R11") (pin "2") (pinfunction "2_2") (pintype "passive"))
    )
    (net (code "45") (name "Net-(Q5-B)") (class "Default")
      (node (ref "C13") (pin "-") (pinfunction "-_-") (pintype "passive"))
      (node (ref "Q5") (pin "1") (pinfunction "B_1") (pintype "passive"))
      (node (ref "R21") (pin "2") (pinfunction "2_2") (pintype "passive"))
    )
    (net (code "46") (name "Net-(Q5-E)") (class "Default")
      (node (ref "C10") (pin "-") (pinfunction "-_-") (pintype "passive"))
      (node (ref "Q5") (pin "3") (pinfunction "E_3") (pintype "passive"))
      (node (ref "R12") (pin "2") (pinfunction "2_2") (pintype "passive"))
    )
    (net (code "47") (name "Net-(Q6-G)") (class "Default")
      (node (ref "C12") (pin "1") (pinfunction "1_1") (pintype "passive"))
      (node (ref "Q6") (pin "2") (pinfunction "G_2") (pintype "passive"))
      (node (ref "R16") (pin "2") (pinfunction "2_2") (pintype "passive"))
    )
    (net (code "48") (name "Net-(Q6-S)") (class "Default")
      (node (ref "C13") (pin "+") (pinfunction "+_+") (pintype "passive"))
      (node (ref "C15") (pin "+") (pinfunction "+_+") (pintype "passive"))
      (node (ref "Q6") (pin "1") (pinfunction "S_1") (pintype "passive"))
      (node (ref "R17") (pin "2") (pinfunction "2_2") (pintype "passive"))
    )
    (net (code "49") (name "Net-(Q7-B)") (class "Default")
      (node (ref "C14") (pin "+") (pinfunction "+_+") (pintype "passive"))
      (node (ref "Q7") (pin "1") (pinfunction "B_1") (pintype "passive"))
      (node (ref "R15") (pin "1") (pinfunction "1_1") (pintype "passive"))
    )
    (net (code "50") (name "Net-(Q8-B)") (class "Default")
      (node (ref "Q8") (pin "2") (pinfunction "B_2") (pintype "passive"))
      (node (ref "R25") (pin "1") (pinfunction "1_1") (pintype "passive"))
      (node (ref "R26") (pin "1") (pinfunction "1_1") (pintype "passive"))
    )
    (net (code "51") (name "Net-(Q8-C)") (class "Default")
      (node (ref "Q8") (pin "1") (pinfunction "C_1") (pintype "passive"))
      (node (ref "R23") (pin "2") (pinfunction "2_2") (pintype "passive"))
      (node (ref "R24") (pin "2") (pinfunction "2_2") (pintype "passive"))
    )
    (net (code "52") (name "Net-(Q9-B)") (class "Default")
      (node (ref "Q9") (pin "2") (pinfunction "B_2") (pintype "passive"))
      (node (ref "R29") (pin "1") (pinfunction "1_1") (pintype "passive"))
    )
    (net (code "53") (name "Net-(Q9-C)") (class "Default")
      (node (ref "Q9") (pin "1") (pinfunction "C_1") (pintype "passive"))
      (node (ref "R26") (pin "2") (pinfunction "2_2") (pintype "passive"))
      (node (ref "R30") (pin "2") (pinfunction "2_2") (pintype "passive"))
      (node (ref "R31") (pin "1") (pinfunction "1_1") (pintype "passive"))
    )
    (net (code "54") (name "Net-(Q10-D)") (class "Default")
      (node (ref "Q10") (pin "3") (pinfunction "D_3") (pintype "passive"))
      (node (ref "R32") (pin "2") (pinfunction "2_2") (pintype "passive"))
      (node (ref "R33") (pin "1") (pinfunction "1_1") (pintype "passive"))
      (node (ref "R44") (pin "2") (pinfunction "2_2") (pintype "passive"))
    )
    (net (code "55") (name "Net-(Q10-G)") (class "Default")
      (node (ref "D5") (pin "A") (pinfunction "A_A") (pintype "passive"))
      (node (ref "Q10") (pin "2") (pinfunction "G_2") (pintype "passive"))
    )
    (net (code "56") (name "Net-(Q10-S)") (class "Default")
      (node (ref "C21") (pin "1") (pinfunction "1_1") (pintype "passive"))
      (node (ref "Q10") (pin "1") (pinfunction "S_1") (pintype "passive"))
      (node (ref "R32") (pin "1") (pinfunction "1_1") (pintype "passive"))
    )
    (net (code "57") (name "Net-(Q11-B)") (class "Default")
      (node (ref "C23") (pin "-") (pinfunction "-_-") (pintype "passive"))
      (node (ref "Q11") (pin "1") (pinfunction "B_1") (pintype "passive"))
      (node (ref "R37") (pin "2") (pinfunction "2_2") (pintype "passive"))
    )
    (net (code "58") (name "Net-(Q11-E)") (class "Default")
      (node (ref "C24") (pin "+") (pinfunction "+_+") (pintype "passive"))
      (node (ref "Q11") (pin "3") (pinfunction "E_3") (pintype "passive"))
      (node (ref "R38") (pin "2") (pinfunction "2_2") (pintype "passive"))
    )
    (net (code "59") (name "Net-(Q12-B)") (class "Default")
      (node (ref "C28") (pin "2") (pinfunction "2_2") (pintype "passive"))
      (node (ref "Q12") (pin "1") (pinfunction "B_1") (pintype "passive"))
      (node (ref "R44") (pin "1") (pinfunction "1_1") (pintype "passive"))
    )
    (net (code "60") (name "Net-(Q12-E)") (class "Default")
      (node (ref "Q12") (pin "3") (pinfunction "E_3") (pintype "passive"))
      (node (ref "R42") (pin "2") (pinfunction "2_2") (pintype "passive"))
      (node (ref "R43") (pin "2") (pinfunction "2_2") (pintype "passive"))
    )
    (net (code "61") (name "Net-(Q13-B)") (class "Default")
      (node (ref "C29") (pin "2") (pinfunction "2_2") (pintype "passive"))
      (node (ref "C30") (pin "-") (pinfunction "-_-") (pintype "passive"))
      (node (ref "Q13") (pin "1") (pinfunction "B_1") (pintype "passive"))
      (node (ref "R35") (pin "2") (pinfunction "2_2") (pintype "passive"))
      (node (ref "R48") (pin "1") (pinfunction "1_1") (pintype "passive"))
    )
    (net (code "62") (name "Net-(Q13-C)") (class "Default")
      (node (ref "C28") (pin "1") (pinfunction "1_1") (pintype "passive"))
      (node (ref "C29") (pin "1") (pinfunction "1_1") (pintype "passive"))
      (node (ref "Q13") (pin "2") (pinfunction "C_2") (pintype "passive"))
      (node (ref "R33") (pin "2") (pinfunction "2_2") (pintype "passive"))
      (node (ref "R45") (pin "1") (pinfunction "1_1") (pintype "passive"))
      (node (ref "R46") (pin "1") (pinfunction "1_1") (pintype "passive"))
      (node (ref "R47") (pin "1") (pinfunction "1_1") (pintype "passive"))
    )
    (net (code "63") (name "Net-(Q13-E)") (class "Default")
      (node (ref "C22") (pin "+") (pinfunction "+_+") (pintype "passive"))
      (node (ref "Q13") (pin "3") (pinfunction "E_3") (pintype "passive"))
      (node (ref "R34") (pin "2") (pinfunction "2_2") (pintype "passive"))
    )
    (net (code "64") (name "Net-(Q14-D)") (class "Default")
      (node (ref "C39") (pin "1") (pinfunction "1_1") (pintype "passive"))
      (node (ref "Q14") (pin "3") (pinfunction "D_3") (pintype "passive"))
      (node (ref "R61") (pin "2") (pinfunction "2_2") (pintype "passive"))
    )
    (net (code "65") (name "Net-(Q14-G)") (class "Default")
      (node (ref "D7") (pin "A") (pinfunction "A_A") (pintype "passive"))
      (node (ref "Q14") (pin "2") (pinfunction "G_2") (pintype "passive"))
    )
    (net (code "66") (name "Net-(Q14-S)") (class "Default")
      (node (ref "Q14") (pin "1") (pinfunction "S_1") (pintype "passive"))
      (node (ref "Q15") (pin "1") (pinfunction "S_1") (pintype "passive"))
      (node (ref "Q16") (pin "2") (pinfunction "G_2") (pintype "passive"))
      (node (ref "R49") (pin "2") (pinfunction "2_2") (pintype "passive"))
    )
    (net (code "67") (name "Net-(Q15-D)") (class "Default")
      (node (ref "Q15") (pin "3") (pinfunction "D_3") (pintype "passive"))
      (node (ref "R64") (pin "2") (pinfunction "2_2") (pintype "passive"))
      (node (ref "R68") (pin "2") (pinfunction "2_2") (pintype "passive"))
    )
    (net (code "68") (name "Net-(Q15-G)") (class "Default")
      (node (ref "D6") (pin "A") (pinfunction "A_A") (pintype "passive"))
      (node (ref "Q15") (pin "2") (pinfunction "G_2") (pintype "passive"))
    )
    (net (code "69") (name "Net-(Q16-D)") (class "Default")
      (node (ref "C31") (pin "2") (pinfunction "2_2") (pintype "passive"))
      (node (ref "Q16") (pin "3") (pinfunction "D_3") (pintype "passive"))
      (node (ref "Q17") (pin "2") (pinfunction "B_2") (pintype "passive"))
      (node (ref "R50") (pin "1") (pinfunction "1_1") (pintype "passive"))
    )
    (net (code "70") (name "Net-(Q16-S)") (class "Default")
      (node (ref "Q16") (pin "1") (pinfunction "S_1") (pintype "passive"))
      (node (ref "Q19") (pin "1") (pinfunction "S_1") (pintype "passive"))
      (node (ref "R53") (pin "2") (pinfunction "2_2") (pintype "passive"))
    )
    (net (code "71") (name "Net-(Q17-C)") (class "Default")
      (node (ref "C31") (pin "1") (pinfunction "1_1") (pintype "passive"))
      (node (ref "Q17") (pin "1") (pinfunction "C_1") (pintype "passive"))
      (node (ref "Q18") (pin "1") (pinfunction "B_1") (pintype "passive"))
      (node (ref "R51") (pin "2") (pinfunction "2_2") (pintype "passive"))
    )
    (net (code "72") (name "Net-(Q18-E)") (class "Default")
      (node (ref "C32") (pin "1") (pinfunction "1_1") (pintype "passive"))
      (node (ref "C35") (pin "+") (pinfunction "+_+") (pintype "passive"))
      (node (ref "Q18") (pin "3") (pinfunction "E_3") (pintype "passive"))
      (node (ref "Q20") (pin "1") (pinfunction "S_1") (pintype "passive"))
      (node (ref "R52") (pin "2") (pinfunction "2_2") (pintype "passive"))
      (node (ref "R56") (pin "2") (pinfunction "2_2") (pintype "passive"))
      (node (ref "VR1") (pin "2") (pinfunction "2_2") (pintype "passive"))
      (node (ref "VR1") (pin "3") (pinfunction "3_3") (pintype "passive"))
    )
    (net (code "73") (name "Net-(Q19-G)") (class "Default")
      (node (ref "C32") (pin "2") (pinfunction "2_2") (pintype "passive"))
      (node (ref "D8") (pin "C") (pinfunction "C_C") (pintype "passive"))
      (node (ref "D9") (pin "A") (pinfunction "A_A") (pintype "passive"))
      (node (ref "Q19") (pin "2") (pinfunction "G_2") (pintype "passive"))
      (node (ref "R54") (pin "2") (pinfunction "2_2") (pintype "passive"))
      (node (ref "R55") (pin "2") (pinfunction "2_2") (pintype "passive"))
    )
    (net (code "74") (name "Net-(Q20-D)") (class "Default")
      (node (ref "C34") (pin "1") (pinfunction "1_1") (pintype "passive"))
      (node (ref "Q20") (pin "3") (pinfunction "D_3") (pintype "passive"))
      (node (ref "R56") (pin "1") (pinfunction "1_1") (pintype "passive"))
    )
    (net (code "75") (name "Net-(Q20-G)") (class "Default")
      (node (ref "D10") (pin "A") (pinfunction "A_A") (pintype "passive"))
      (node (ref "Q20") (pin "2") (pinfunction "G_2") (pintype "passive"))
    )
    (net (code "76") (name "Net-(Q21-D)") (class "Default")
      (node (ref "C15") (pin "-") (pinfunction "-_-") (pintype "passive"))
      (node (ref "Q21") (pin "3") (pinfunction "D_3") (pintype "passive"))
      (node (ref "R18") (pin "2") (pinfunction "2_2") (pintype "passive"))
    )
    (net (code "77") (name "Net-(Q21-G)") (class "Default")
      (node (ref "D13") (pin "A") (pinfunction "A_A") (pintype "passive"))
      (node (ref "Q21") (pin "2") (pinfunction "G_2") (pintype "passive"))
    )
    (net (code "78") (name "Net-(Q21-S)") (class "Default")
      (node (ref "C38") (pin "+") (pinfunction "+_+") (pintype "passive"))
      (node (ref "Q21") (pin "1") (pinfunction "S_1") (pintype "passive"))
      (node (ref "R60") (pin "2") (pinfunction "2_2") (pintype "passive"))
    )
    (net (code "79") (name "Net-(Q22-B)") (class "Default")
      (node (ref "C40") (pin "1") (pinfunction "1_1") (pintype "passive"))
      (node (ref "Q22") (pin "1") (pinfunction "B_1") (pintype "passive"))
      (node (ref "R63") (pin "2") (pinfunction "2_2") (pintype "passive"))
    )
    (net (code "80") (name "Net-(Q22-C)") (class "Default")
      (node (ref "C39") (pin "2") (pinfunction "2_2") (pintype "passive"))
      (node (ref "C41") (pin "2") (pinfunction "2_2") (pintype "passive"))
      (node (ref "Q22") (pin "2") (pinfunction "C_2") (pintype "passive"))
      (node (ref "R65") (pin "1") (pinfunction "1_1") (pintype "passive"))
      (node (ref "R69") (pin "1") (pinfunction "1_1") (pintype "passive"))
    )
    (net (code "81") (name "Net-(Q22-E)") (class "Default")
      (node (ref "Q22") (pin "3") (pinfunction "E_3") (pintype "passive"))
      (node (ref "R66") (pin "2") (pinfunction "2_2") (pintype "passive"))
      (node (ref "R67") (pin "2") (pinfunction "2_2") (pintype "passive"))
    )
    (net (code "82") (name "Net-(Q23-B)") (class "Default")
      (node (ref "C44") (pin "1") (pinfunction "1_1") (pintype "passive"))
      (node (ref "Q23") (pin "1") (pinfunction "B_1") (pintype "passive"))
      (node (ref "R70") (pin "2") (pinfunction "2_2") (pintype "passive"))
    )
    (net (code "83") (name "Net-(Q23-E)") (class "Default")
      (node (ref "C43") (pin "2") (pinfunction "2_2") (pintype "passive"))
      (node (ref "C45") (pin "2") (pinfunction "2_2") (pintype "passive"))
      (node (ref "Q23") (pin "3") (pinfunction "E_3") (pintype "passive"))
      (node (ref "R72") (pin "2") (pinfunction "2_2") (pintype "passive"))
    )
    (net (code "84") (name "Net-(R45-Pad2)") (class "Default")
      (node (ref "R45") (pin "2") (pinfunction "2_2") (pintype "passive"))
      (node (ref "VR2") (pin "1") (pinfunction "1_1") (pintype "passive"))
    )
    (net (code "85") (name "Net-(R55-Pad1)") (class "Default")
      (node (ref "R55") (pin "1") (pinfunction "1_1") (pintype "passive"))
      (node (ref "VR1") (pin "1") (pinfunction "1_1") (pintype "passive"))
    )
    (net (code "86") (name "Net-(R59-Pad2)") (class "Default")
      (node (ref "R59") (pin "2") (pinfunction "2_2") (pintype "passive"))
      (node (ref "VR2") (pin "3") (pinfunction "3_3") (pintype "passive"))
    )
    (net (code "87") (name "Net-(SW1-P)") (class "Default")
      (node (ref "R1 ") (pin "2") (pinfunction "2_2") (pintype "passive"))
      (node (ref "SW1") (pin "2") (pinfunction "P_2") (pintype "passive"))
    )
    (net (code "88") (name "VA") (class "Default")
      (node (ref "C16") (pin "+") (pinfunction "+_+") (pintype "passive"))
      (node (ref "Q11") (pin "2") (pinfunction "C_2") (pintype "passive"))
      (node (ref "Q12") (pin "2") (pinfunction "C_2") (pintype "passive"))
      (node (ref "Q17") (pin "3") (pinfunction "E_3") (pintype "passive"))
      (node (ref "Q18") (pin "2") (pinfunction "C_2") (pintype "passive"))
      (node (ref "Q19") (pin "3") (pinfunction "D_3") (pintype "passive"))
      (node (ref "Q23") (pin "2") (pinfunction "C_2") (pintype "passive"))
      (node (ref "Q5") (pin "2") (pinfunction "C_2") (pintype "passive"))
      (node (ref "Q6") (pin "3") (pinfunction "D_3") (pintype "passive"))
      (node (ref "Q7") (pin "3") (pinfunction "E_3") (pintype "passive"))
      (node (ref "R20") (pin "2") (pinfunction "2_2") (pintype "passive"))
      (node (ref "R47") (pin "2") (pinfunction "2_2") (pintype "passive"))
      (node (ref "R48") (pin "2") (pinfunction "2_2") (pintype "passive"))
      (node (ref "R50") (pin "2") (pinfunction "2_2") (pintype "passive"))
      (node (ref "R65") (pin "2") (pinfunction "2_2") (pintype "passive"))
    )
    (net (code "89") (name "VB") (class "Default")
      (node (ref "C17") (pin "+") (pinfunction "+_+") (pintype "passive"))
      (node (ref "R11") (pin "1") (pinfunction "1_1") (pintype "passive"))
      (node (ref "R14") (pin "1") (pinfunction "1_1") (pintype "passive"))
      (node (ref "R16") (pin "1") (pinfunction "1_1") (pintype "passive"))
      (node (ref "R18") (pin "1") (pinfunction "1_1") (pintype "passive"))
      (node (ref "R19") (pin "2") (pinfunction "2_2") (pintype "passive"))
      (node (ref "R20") (pin "1") (pinfunction "1_1") (pintype "passive"))
      (node (ref "R21") (pin "1") (pinfunction "1_1") (pintype "passive"))
      (node (ref "R36") (pin "1") (pinfunction "1_1") (pintype "passive"))
      (node (ref "R37") (pin "1") (pinfunction "1_1") (pintype "passive"))
      (node (ref "R49") (pin "1") (pinfunction "1_1") (pintype "passive"))
      (node (ref "R60") (pin "1") (pinfunction "1_1") (pintype "passive"))
      (node (ref "R61") (pin "1") (pinfunction "1_1") (pintype "passive"))
      (node (ref "R63") (pin "1") (pinfunction "1_1") (pintype "passive"))
      (node (ref "R71") (pin "1") (pinfunction "1_1") (pintype "passive"))
    )
    (net (code "90") (name "unconnected-(SW1-S-Pad3)") (class "Default")
      (node (ref "SW1") (pin "3") (pinfunction "S_3") (pintype "passive"))
    )
  )
)
